# 555timer.net
KiCad netlist of a schematic drawn in EAGLE
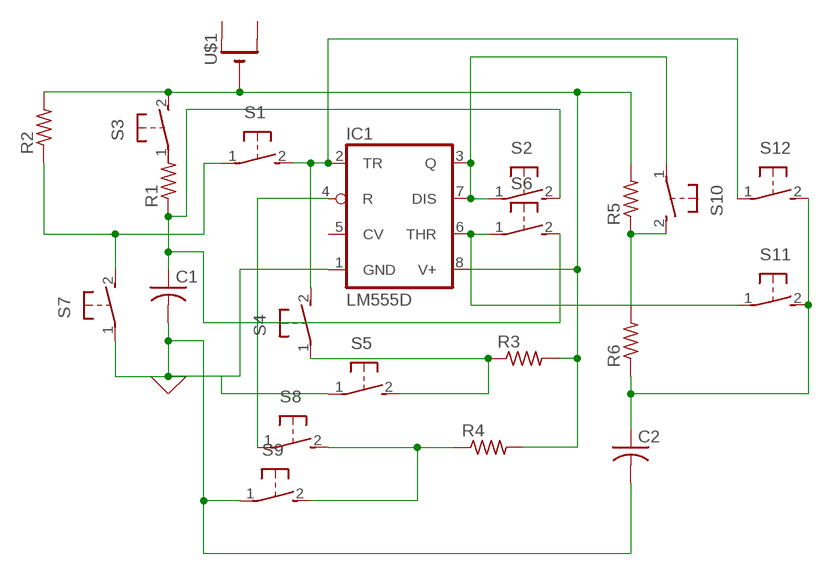
[diagram p0: schematic, sheet 1]

(export (version "E")
  (design (tool "Eeschema 10.0.6"))
  (components
    (comp (ref "C1")
      (value "C-US025-025X050")
      (footprint "eagle-import:C025-025X050")
      (libsource (lib "eagle-import") (part "C-US025-025X050"))
    )
    (comp (ref "C2")
      (value "C-US025-025X050")
      (footprint "eagle-import:C025-025X050")
      (libsource (lib "eagle-import") (part "C-US025-025X050"))
    )
    (comp (ref "IC1")
      (value "LM555D")
      (footprint "eagle-import:SO08")
      (libsource (lib "eagle-import") (part "555DLM"))
    )
    (comp (ref "R1")
      (value "R-US_0411/15")
      (footprint "eagle-import:0411_15")
      (libsource (lib "eagle-import") (part "R-US_0411/15"))
    )
    (comp (ref "R2")
      (value "R-US_0411/15")
      (footprint "eagle-import:0411_15")
      (libsource (lib "eagle-import") (part "R-US_0411/15"))
    )
    (comp (ref "R3")
      (value "R-US_0411/15")
      (footprint "eagle-import:0411_15")
      (libsource (lib "eagle-import") (part "R-US_0411/15"))
    )
    (comp (ref "R4")
      (value "R-US_0411/15")
      (footprint "eagle-import:0411_15")
      (libsource (lib "eagle-import") (part "R-US_0411/15"))
    )
    (comp (ref "R5")
      (value "R-US_0411/15")
      (footprint "eagle-import:0411_15")
      (libsource (lib "eagle-import") (part "R-US_0411/15"))
    )
    (comp (ref "R6")
      (value "R-US_0411/15")
      (footprint "eagle-import:0411_15")
      (libsource (lib "eagle-import") (part "R-US_0411/15"))
    )
    (comp (ref "S1")
      (value "31-XX")
      (footprint "eagle-import:B3F-31XX")
      (libsource (lib "eagle-import") (part "31-XX"))
    )
    (comp (ref "S2")
      (value "31-XX")
      (footprint "eagle-import:B3F-31XX")
      (libsource (lib "eagle-import") (part "31-XX"))
    )
    (comp (ref "S3")
      (value "31-XX")
      (footprint "eagle-import:B3F-31XX")
      (libsource (lib "eagle-import") (part "31-XX"))
    )
    (comp (ref "S4")
      (value "31-XX")
      (footprint "eagle-import:B3F-31XX")
      (libsource (lib "eagle-import") (part "31-XX"))
    )
    (comp (ref "S5")
      (value "31-XX")
      (footprint "eagle-import:B3F-31XX")
      (libsource (lib "eagle-import") (part "31-XX"))
    )
    (comp (ref "S6")
      (value "31-XX")
      (footprint "eagle-import:B3F-31XX")
      (libsource (lib "eagle-import") (part "31-XX"))
    )
    (comp (ref "S7")
      (value "31-XX")
      (footprint "eagle-import:B3F-31XX")
      (libsource (lib "eagle-import") (part "31-XX"))
    )
    (comp (ref "S8")
      (value "31-XX")
      (footprint "eagle-import:B3F-31XX")
      (libsource (lib "eagle-import") (part "31-XX"))
    )
    (comp (ref "S9")
      (value "31-XX")
      (footprint "eagle-import:B3F-31XX")
      (libsource (lib "eagle-import") (part "31-XX"))
    )
    (comp (ref "S10")
      (value "31-XX")
      (footprint "eagle-import:B3F-31XX")
      (libsource (lib "eagle-import") (part "31-XX"))
    )
    (comp (ref "S11")
      (value "31-XX")
      (footprint "eagle-import:B3F-31XX")
      (libsource (lib "eagle-import") (part "31-XX"))
    )
    (comp (ref "S12")
      (value "31-XX")
      (footprint "eagle-import:B3F-31XX")
      (libsource (lib "eagle-import") (part "31-XX"))
    )
    (comp (ref "U$1")
      (value "CR1220SMT")
      (footprint "eagle-import:CR1220-SMD")
      (libsource (lib "eagle-import") (part "CR1220SMT"))
    )
  )
  (nets
    (net (code "1") (name "GND") (class "Default")
      (node (ref "C1") (pin "2") (pinfunction "2_2") (pintype "passive"))
      (node (ref "C2") (pin "2") (pinfunction "2_2") (pintype "passive"))
      (node (ref "IC1") (pin "1") (pinfunction "GND_1") (pintype "power_in"))
      (node (ref "S5") (pin "1") (pinfunction "P_1") (pintype "passive"))
      (node (ref "S7") (pin "1") (pinfunction "P_1") (pintype "passive"))
      (node (ref "S9") (pin "1") (pinfunction "P_1") (pintype "passive"))
    )
    (net (code "2") (name "Net-(IC1-DIS)") (class "Default")
      (node (ref "IC1") (pin "3") (pinfunction "Q_3") (pintype "output"))
      (node (ref "IC1") (pin "7") (pinfunction "DIS_7") (pintype "input"))
      (node (ref "S10") (pin "1") (pinfunction "P_1") (pintype "passive"))
      (node (ref "S2") (pin "1") (pinfunction "P_1") (pintype "passive"))
    )
    (net (code "3") (name "Net-(IC1-R)") (class "Default")
      (node (ref "IC1") (pin "4") (pinfunction "R_4") (pintype "input"))
      (node (ref "S8") (pin "1") (pinfunction "P_1") (pintype "passive"))
    )
    (net (code "4") (name "Net-(IC1-THR)") (class "Default")
      (node (ref "IC1") (pin "6") (pinfunction "THR_6") (pintype "input"))
      (node (ref "S11") (pin "1") (pinfunction "P_1") (pintype "passive"))
      (node (ref "S6") (pin "1") (pinfunction "P_1") (pintype "passive"))
    )
    (net (code "5") (name "Net-(IC1-TR)") (class "Default")
      (node (ref "IC1") (pin "2") (pinfunction "TR_2") (pintype "input"))
      (node (ref "S1") (pin "2") (pinfunction "S_2") (pintype "passive"))
      (node (ref "S12") (pin "1") (pinfunction "P_1") (pintype "passive"))
      (node (ref "S4") (pin "2") (pinfunction "S_2") (pintype "passive"))
    )
    (net (code "6") (name "Net-(IC1-V+)") (class "Default")
      (node (ref "IC1") (pin "8") (pinfunction "V+_8") (pintype "power_in"))
      (node (ref "R2") (pin "2") (pinfunction "2_2") (pintype "passive"))
      (node (ref "R3") (pin "2") (pinfunction "2_2") (pintype "passive"))
      (node (ref "R4") (pin "2") (pinfunction "2_2") (pintype "passive"))
      (node (ref "R5") (pin "2") (pinfunction "2_2") (pintype "passive"))
      (node (ref "S3") (pin "2") (pinfunction "S_2") (pintype "passive"))
      (node (ref "U$1") (pin "-") (pinfunction "-_-") (pintype "passive"))
    )
    (net (code "7") (name "Net-(S1-P)") (class "Default")
      (node (ref "R2") (pin "1") (pinfunction "1_1") (pintype "passive"))
      (node (ref "S1") (pin "1") (pinfunction "P_1") (pintype "passive"))
      (node (ref "S7") (pin "2") (pinfunction "S_2") (pintype "passive"))
    )
    (net (code "8") (name "Net-(S2-S)") (class "Default")
      (node (ref "C1") (pin "1") (pinfunction "1_1") (pintype "passive"))
      (node (ref "R1") (pin "1") (pinfunction "1_1") (pintype "passive"))
      (node (ref "S2") (pin "2") (pinfunction "S_2") (pintype "passive"))
      (node (ref "S6") (pin "2") (pinfunction "S_2") (pintype "passive"))
    )
    (net (code "9") (name "Net-(S4-P)") (class "Default")
      (node (ref "R3") (pin "1") (pinfunction "1_1") (pintype "passive"))
      (node (ref "S4") (pin "1") (pinfunction "P_1") (pintype "passive"))
      (node (ref "S5") (pin "2") (pinfunction "S_2") (pintype "passive"))
    )
    (net (code "10") (name "Net-(S8-S)") (class "Default")
      (node (ref "R4") (pin "1") (pinfunction "1_1") (pintype "passive"))
      (node (ref "S8") (pin "2") (pinfunction "S_2") (pintype "passive"))
      (node (ref "S9") (pin "2") (pinfunction "S_2") (pintype "passive"))
    )
    (net (code "11") (name "Net-(S10-S)") (class "Default")
      (node (ref "R5") (pin "1") (pinfunction "1_1") (pintype "passive"))
      (node (ref "R6") (pin "2") (pinfunction "2_2") (pintype "passive"))
      (node (ref "S10") (pin "2") (pinfunction "S_2") (pintype "passive"))
    )
    (net (code "12") (name "Net-(S11-S)") (class "Default")
      (node (ref "C2") (pin "1") (pinfunction "1_1") (pintype "passive"))
      (node (ref "R6") (pin "1") (pinfunction "1_1") (pintype "passive"))
      (node (ref "S11") (pin "2") (pinfunction "S_2") (pintype "passive"))
      (node (ref "S12") (pin "2") (pinfunction "S_2") (pintype "passive"))
    )
    (net (code "13") (name "unconnected-(IC1-CV-Pad5)") (class "Default")
      (node (ref "IC1") (pin "5") (pinfunction "CV_5") (pintype "input"))
    )
    (net (code "14") (name "unconnected-(R1-Pad2)") (class "Default")
      (node (ref "R1") (pin "2") (pinfunction "2_2") (pintype "passive"))
    )
    (net (code "15") (name "unconnected-(S3-P-Pad1)") (class "Default")
      (node (ref "S3") (pin "1") (pinfunction "P_1") (pintype "passive"))
    )
    (net (code "16") (name "unconnected-(U$1-+-Pad+$1)") (class "Default")
      (node (ref "U$1") (pin "+$1") (pinfunction "+_+$1") (pintype "passive"))
    )
    (net (code "17") (name "unconnected-(U$1-+1-Pad+$2)") (class "Default")
      (node (ref "U$1") (pin "+$2") (pinfunction "+1_+$2") (pintype "passive"))
    )
  )
)
